# PX4FLOW1_3_1.net
KiCad netlist of a schematic drawn in EAGLE
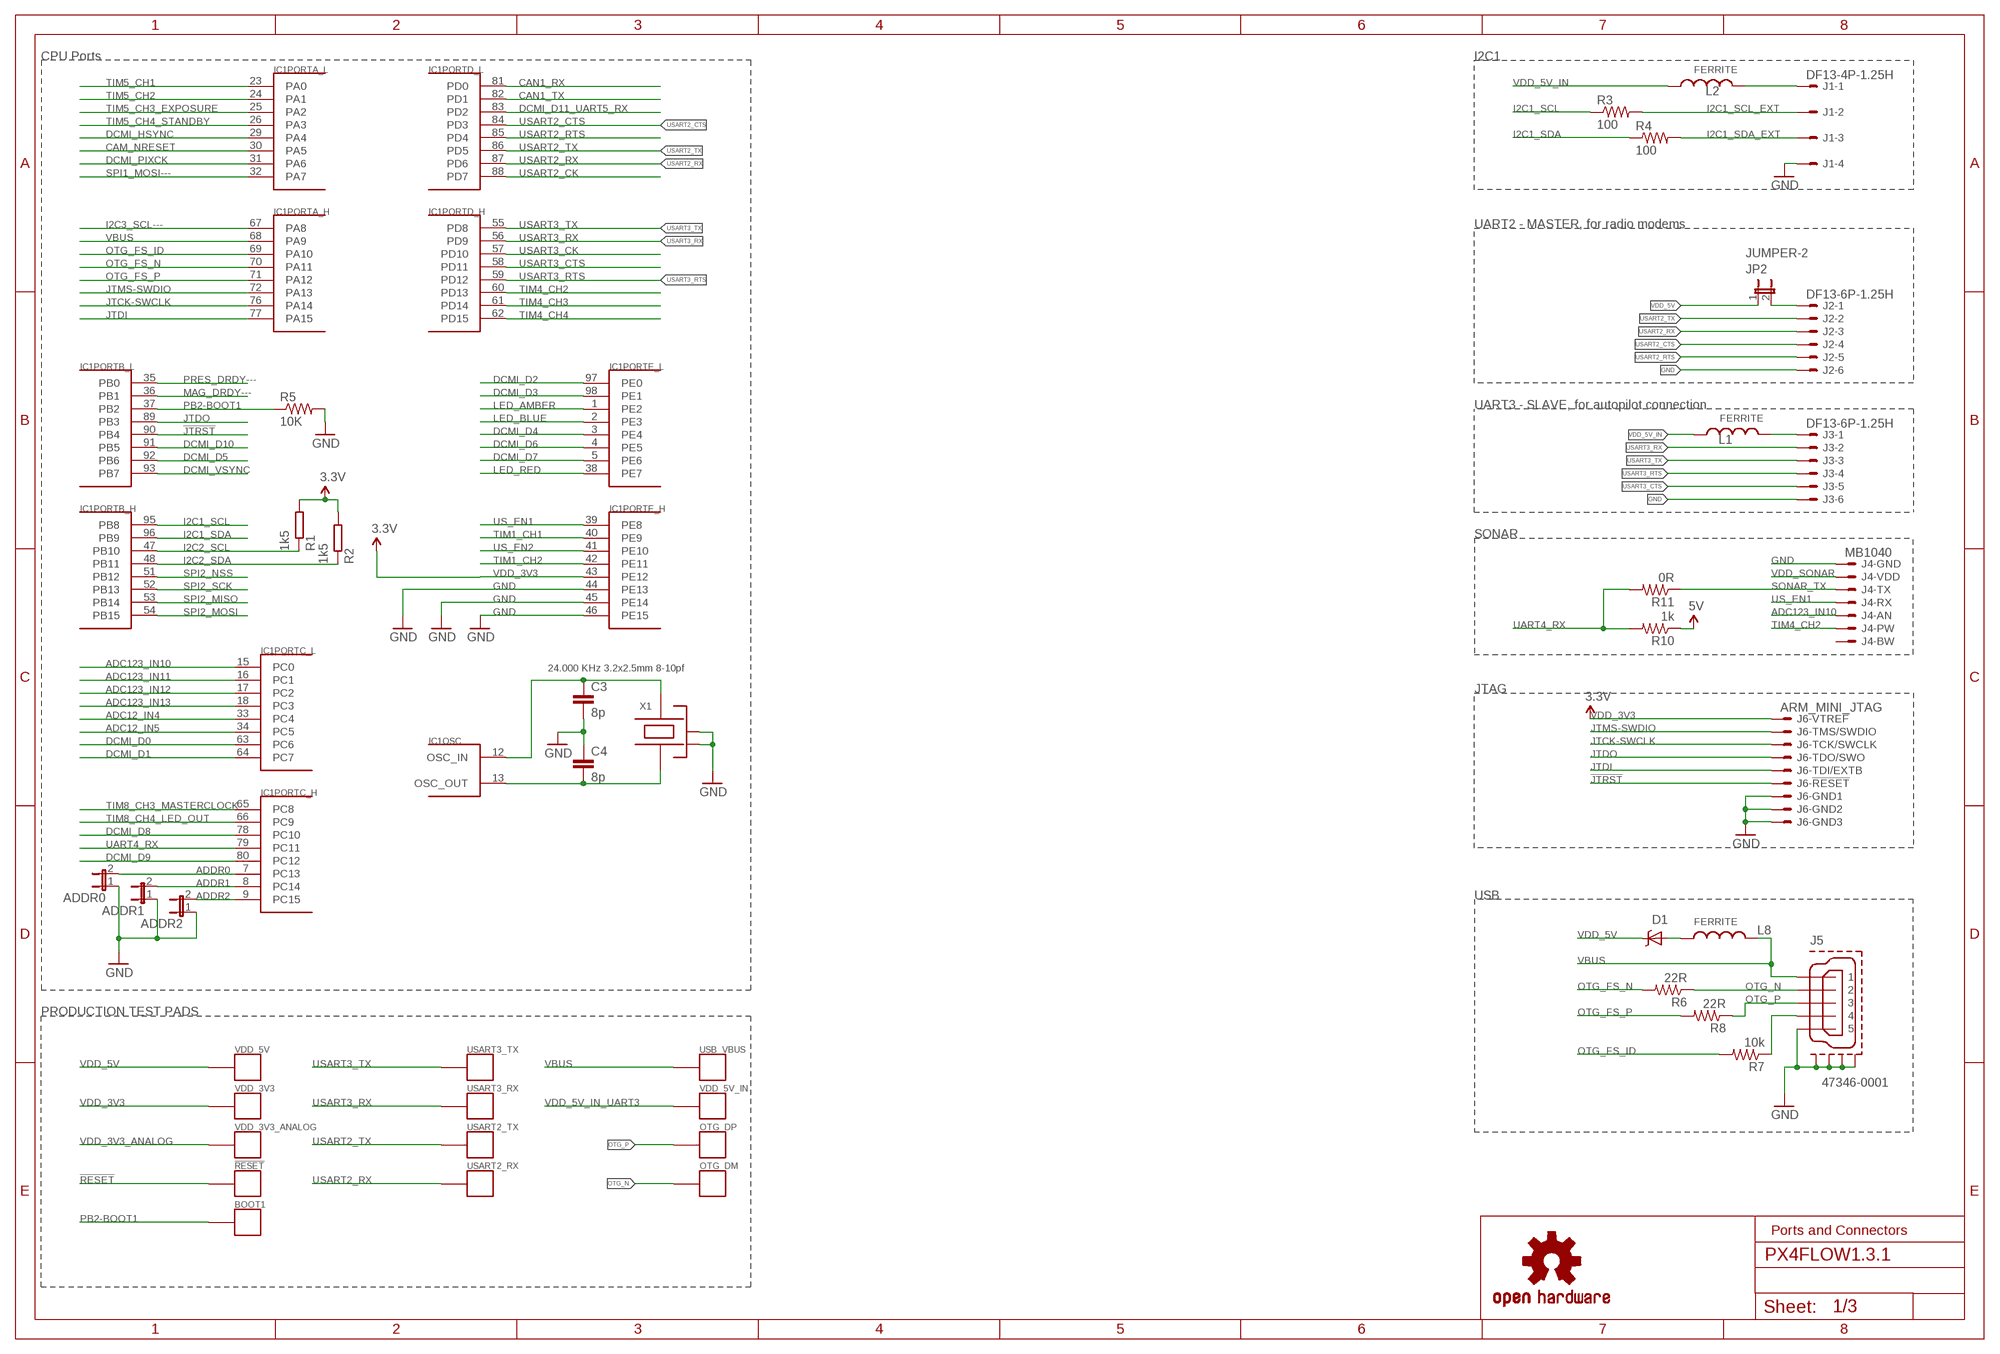
[diagram p0: schematic, sheet 1]
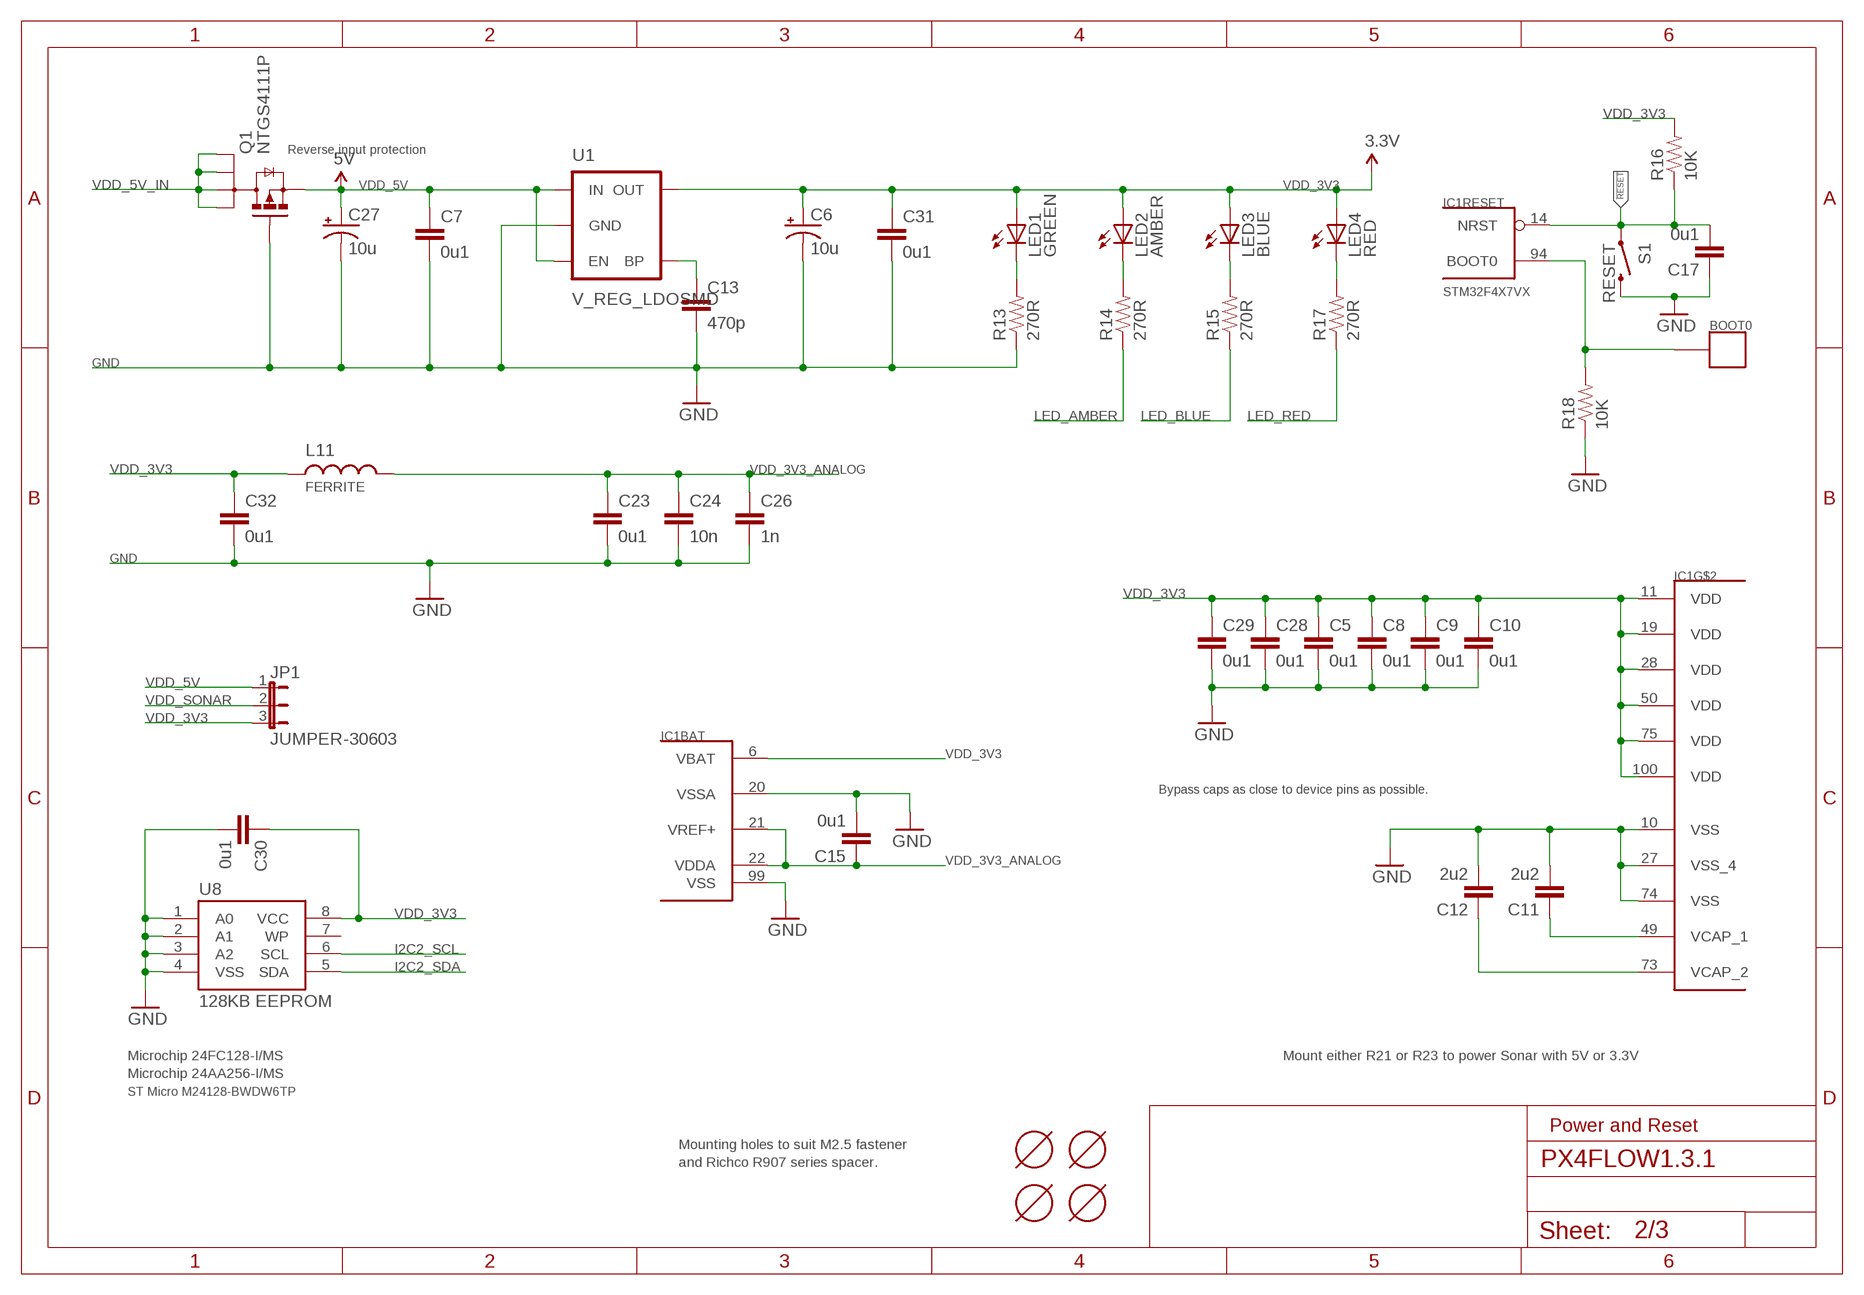
[diagram p1: schematic, sheet 2]
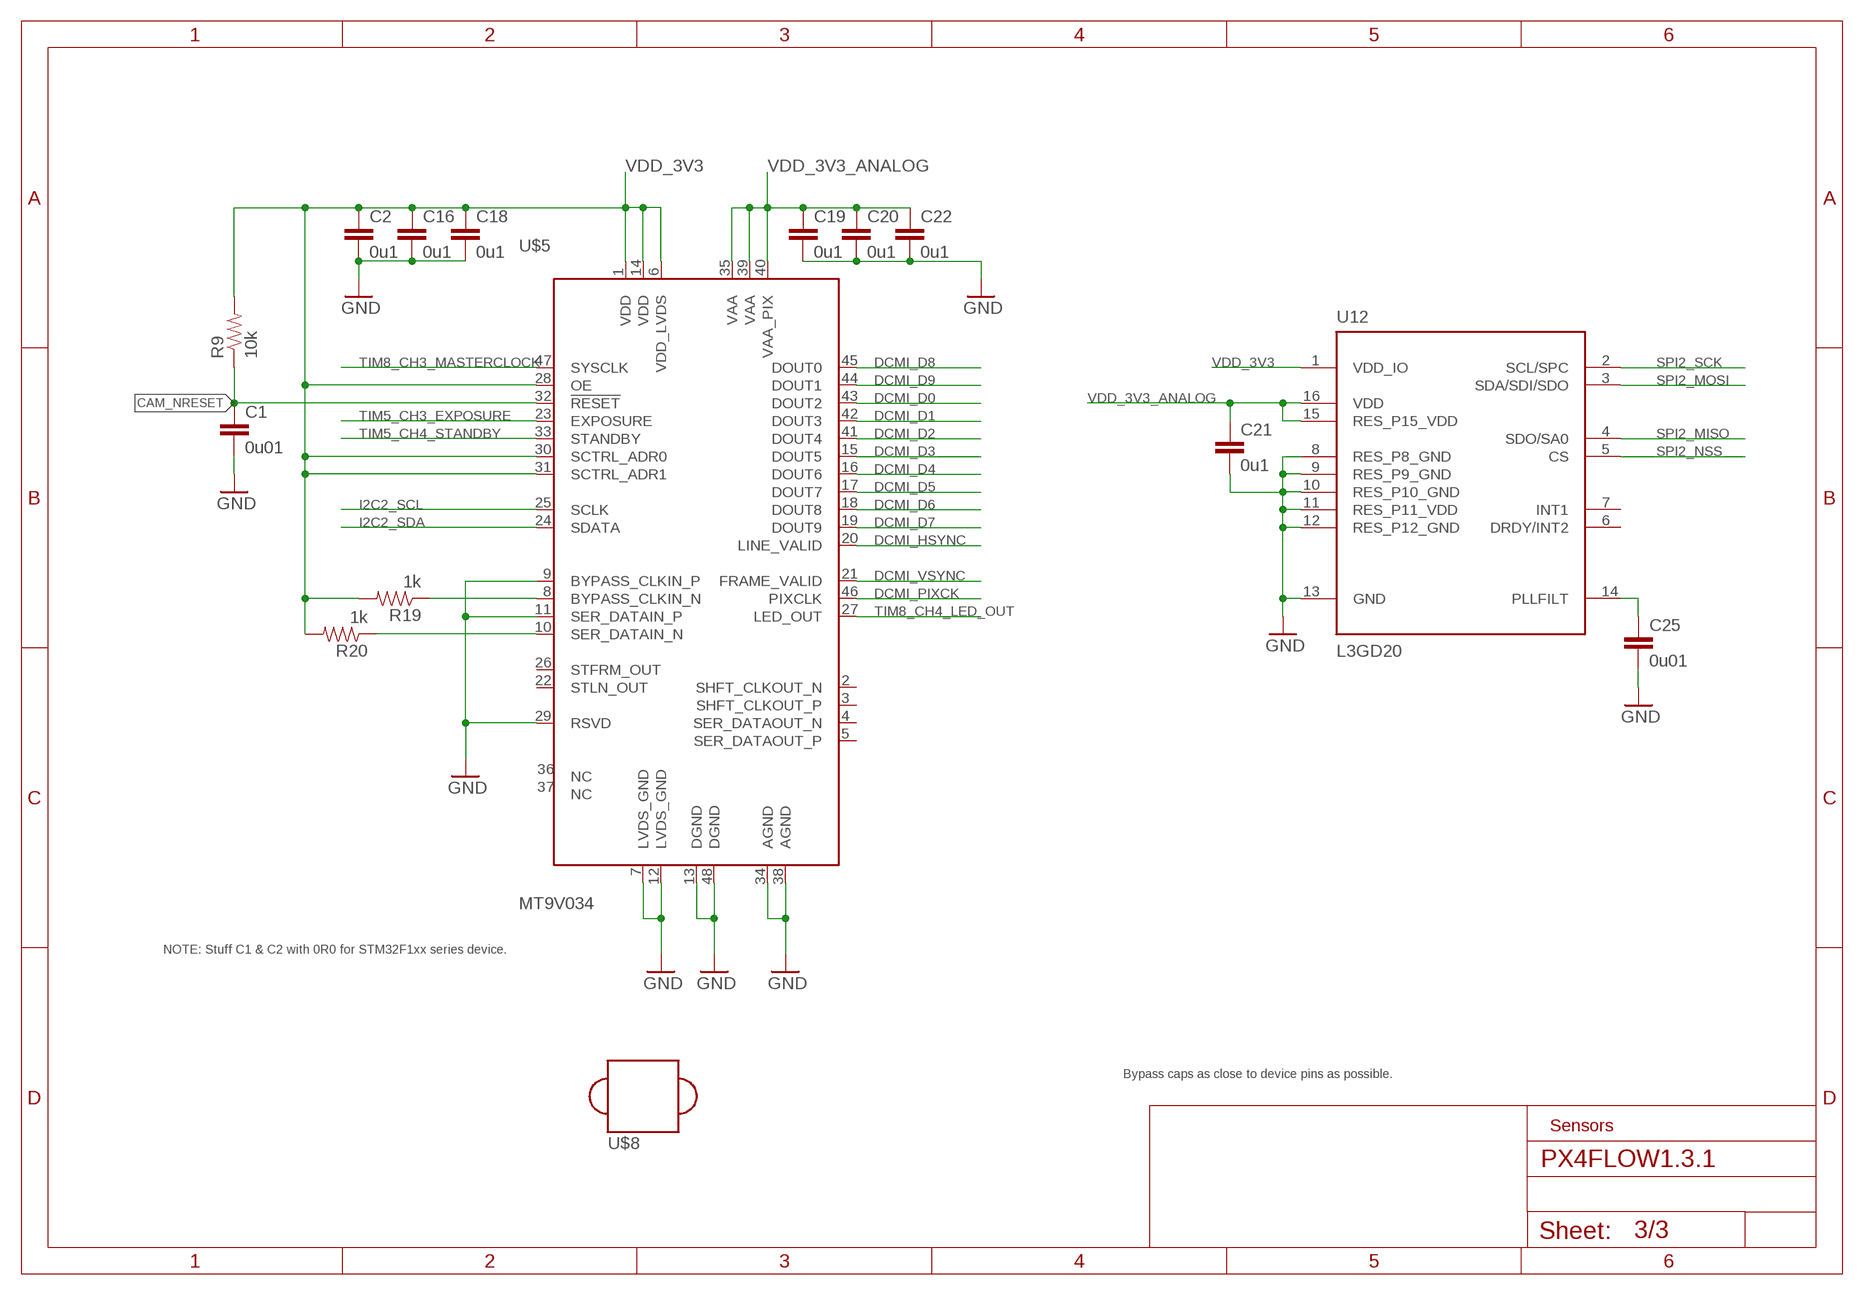
[diagram p2: schematic, sheet 3]

(export (version "E")
  (design (tool "Eeschema 10.0.6"))
  (components
    (comp (ref "BOOT0")
      (value "PAD.05")
      (footprint "eagle-import:PAD.05X.05")
      (libsource (lib "eagle-import") (part "PAD.05"))
    )
    (comp (ref "C5")
      (value "0u1")
      (footprint "eagle-import:0402-CAP")
      (fields (field (name "PARTNO") "CC0402ZRY5V7BB104"))
      (libsource (lib "eagle-import") (part "CAP0402-CAP"))
    )
    (comp (ref "C6")
      (value "10u")
      (footprint "eagle-import:EIA3216")
      (fields (field (name "PARTNO") "F931A106MAA"))
      (libsource (lib "eagle-import") (part "CAP_POL1206"))
    )
    (comp (ref "C7")
      (value "0u1")
      (footprint "eagle-import:0402-CAP")
      (fields (field (name "PARTNO") "CC0402ZRY5V7BB104"))
      (libsource (lib "eagle-import") (part "CAP0402-CAP"))
    )
    (comp (ref "C8")
      (value "0u1")
      (footprint "eagle-import:0402-CAP")
      (fields (field (name "PARTNO") "CC0402ZRY5V7BB104"))
      (libsource (lib "eagle-import") (part "CAP0402-CAP"))
    )
    (comp (ref "C9")
      (value "0u1")
      (footprint "eagle-import:0402-CAP")
      (fields (field (name "PARTNO") "CC0402ZRY5V7BB104"))
      (libsource (lib "eagle-import") (part "CAP0402-CAP"))
    )
    (comp (ref "C10")
      (value "0u1")
      (footprint "eagle-import:0402-CAP")
      (fields (field (name "PARTNO") "CC0402ZRY5V7BB104"))
      (libsource (lib "eagle-import") (part "CAP0402-CAP"))
    )
    (comp (ref "C11")
      (value "2u2")
      (footprint "eagle-import:0402-CAP")
      (fields (field (name "PARTNO") "C1608Y5V1C225Z"))
      (libsource (lib "eagle-import") (part "CAP0402-CAP"))
    )
    (comp (ref "C12")
      (value "2u2")
      (footprint "eagle-import:0402-CAP")
      (fields (field (name "PARTNO") "C1608Y5V1C225Z"))
      (libsource (lib "eagle-import") (part "CAP0402-CAP"))
    )
    (comp (ref "C13")
      (value "470p")
      (footprint "eagle-import:0402-CAP")
      (fields (field (name "PARTNO") "CC0402KRX7R9BB471"))
      (libsource (lib "eagle-import") (part "CAP0402-CAP"))
    )
    (comp (ref "C15")
      (value "0u1")
      (footprint "eagle-import:0402-CAP")
      (fields (field (name "PARTNO") "CC0402ZRY5V7BB104"))
      (libsource (lib "eagle-import") (part "CAP0402-CAP"))
    )
    (comp (ref "C17")
      (value "0u1")
      (footprint "eagle-import:0402-CAP")
      (fields (field (name "PARTNO") "CC0402ZRY5V7BB104"))
      (libsource (lib "eagle-import") (part "CAP0402-CAP"))
    )
    (comp (ref "C23")
      (value "0u1")
      (footprint "eagle-import:0402-CAP")
      (fields (field (name "PARTNO") "CC0402ZRY5V7BB104"))
      (libsource (lib "eagle-import") (part "CAP0402-CAP"))
    )
    (comp (ref "C24")
      (value "10n")
      (footprint "eagle-import:0402-CAP")
      (fields (field (name "PARTNO") "CC0402ZRY5V7BB104"))
      (libsource (lib "eagle-import") (part "CAP0402-CAP"))
    )
    (comp (ref "C26")
      (value "1n")
      (footprint "eagle-import:0402-CAP")
      (fields (field (name "PARTNO") "CC0402ZRY5V7BB104"))
      (libsource (lib "eagle-import") (part "CAP0402-CAP"))
    )
    (comp (ref "C27")
      (value "10u")
      (footprint "eagle-import:EIA3216")
      (fields (field (name "PARTNO") "F931A106MAA"))
      (libsource (lib "eagle-import") (part "CAP_POL1206"))
    )
    (comp (ref "C28")
      (value "0u1")
      (footprint "eagle-import:0402-CAP")
      (fields (field (name "PARTNO") "CC0402ZRY5V7BB104"))
      (libsource (lib "eagle-import") (part "CAP0402-CAP"))
    )
    (comp (ref "C29")
      (value "0u1")
      (footprint "eagle-import:0402-CAP")
      (fields (field (name "PARTNO") "CC0402ZRY5V7BB104"))
      (libsource (lib "eagle-import") (part "CAP0402-CAP"))
    )
    (comp (ref "C30")
      (value "0u1")
      (footprint "eagle-import:0402-CAP")
      (fields (field (name "PARTNO") "CC0402ZRY5V7BB104"))
      (libsource (lib "eagle-import") (part "CAP0402-CAP"))
    )
    (comp (ref "C31")
      (value "0u1")
      (footprint "eagle-import:0402-CAP")
      (fields (field (name "PARTNO") "CC0402ZRY5V7BB104"))
      (libsource (lib "eagle-import") (part "CAP0402-CAP"))
    )
    (comp (ref "C32")
      (value "0u1")
      (footprint "eagle-import:0402-CAP")
      (fields (field (name "PARTNO") "CC0402ZRY5V7BB104"))
      (libsource (lib "eagle-import") (part "CAP0402-CAP"))
    )
    (comp (ref "IC1")
      (value "STM32F4X7VX")
      (footprint "eagle-import:TQFP100")
      (fields (field (name "PARTNO") "STM32F407VGT6"))
      (libsource (lib "eagle-import") (part "STM32F4X7VX"))
    )
    (comp (ref "JP1")
      (value "JUMPER-30603")
      (footprint "eagle-import:SJ_3_0603_PASTE1&2")
      (fields (field (name "PARTNO") "RMCF0402ZT0R00"))
      (libsource (lib "eagle-import") (part "JUMPER-30603"))
    )
    (comp (ref "L11")
      (value "FERRITE")
      (footprint "eagle-import:0402-IND")
      (fields (field (name "PARTNO") "BKP1005HS121-T"))
      (libsource (lib "eagle-import") (part "INDUCTOR0402"))
    )
    (comp (ref "LED1")
      (value "GREEN")
      (footprint "eagle-import:LED-0603")
      (fields (field (name "PARTNO") "LNJ337W83RA"))
      (libsource (lib "eagle-import") (part "LED0603"))
    )
    (comp (ref "LED2")
      (value "AMBER")
      (footprint "eagle-import:LED-0603")
      (fields (field (name "PARTNO") "LNJ437W84RA"))
      (libsource (lib "eagle-import") (part "LED0603"))
    )
    (comp (ref "LED3")
      (value "BLUE")
      (footprint "eagle-import:LED-0603")
      (fields (field (name "PARTNO") "LNJ937W8CRA"))
      (libsource (lib "eagle-import") (part "LED0603"))
    )
    (comp (ref "LED4")
      (value "RED")
      (footprint "eagle-import:LED-0603")
      (fields (field (name "PARTNO") "LNJ237W82RA"))
      (libsource (lib "eagle-import") (part "LED0603"))
    )
    (comp (ref "Q1")
      (value "NTGS4111P")
      (footprint "eagle-import:TSOP-6")
      (libsource (lib "eagle-import") (part "NTGS4111P"))
    )
    (comp (ref "R13")
      (value "270R")
      (footprint "eagle-import:0402-RES")
      (fields (field (name "PARTNO") "MCR01MZPJ271"))
      (libsource (lib "eagle-import") (part "RESISTOR0402-RES"))
    )
    (comp (ref "R14")
      (value "270R")
      (footprint "eagle-import:0402-RES")
      (fields (field (name "PARTNO") "MCR01MZPJ271"))
      (libsource (lib "eagle-import") (part "RESISTOR0402-RES"))
    )
    (comp (ref "R15")
      (value "270R")
      (footprint "eagle-import:0402-RES")
      (fields (field (name "PARTNO") "MCR01MZPJ820"))
      (libsource (lib "eagle-import") (part "RESISTOR0402-RES"))
    )
    (comp (ref "R16")
      (value "10K")
      (footprint "eagle-import:0402-RES")
      (fields (field (name "PARTNO") "RMCF0402FT10K0"))
      (libsource (lib "eagle-import") (part "RESISTOR0402-RES"))
    )
    (comp (ref "R17")
      (value "270R")
      (footprint "eagle-import:0402-RES")
      (fields (field (name "PARTNO") "MCR01MZPJ820"))
      (libsource (lib "eagle-import") (part "RESISTOR0402-RES"))
    )
    (comp (ref "R18")
      (value "10K")
      (footprint "eagle-import:0402-RES")
      (fields (field (name "PARTNO") "RMCF0402FT10K0"))
      (libsource (lib "eagle-import") (part "RESISTOR0402-RES"))
    )
    (comp (ref "S1")
      (value "RESET")
      (footprint "eagle-import:EVQP7J01K")
      (fields (field (name "PARTNO") "EVQP7J01K"))
      (libsource (lib "eagle-import") (part "SWITCH-MOMENTARY-2"))
    )
    (comp (ref "U$1")
      (value "MOUNT-HOLE3.1MM")
      (footprint "eagle-import:MOUNT-HOLE3.1")
      (libsource (lib "eagle-import") (part "MOUNT-HOLE3.1MM"))
    )
    (comp (ref "U$2")
      (value "MOUNT-HOLE3.1MM")
      (footprint "eagle-import:MOUNT-HOLE3.1")
      (libsource (lib "eagle-import") (part "MOUNT-HOLE3.1MM"))
    )
    (comp (ref "U$3")
      (value "MOUNT-HOLE3.1MM")
      (footprint "eagle-import:MOUNT-HOLE3.1")
      (libsource (lib "eagle-import") (part "MOUNT-HOLE3.1MM"))
    )
    (comp (ref "U$4")
      (value "MOUNT-HOLE3.1MM")
      (footprint "eagle-import:MOUNT-HOLE3.1")
      (libsource (lib "eagle-import") (part "MOUNT-HOLE3.1MM"))
    )
    (comp (ref "U1")
      (value "V_REG_LDOSMD")
      (footprint "eagle-import:SOT23-5")
      (fields (field (name "PARTNO") "MIC5207-3.3YM5"))
      (libsource (lib "eagle-import") (part "V_REG_LDOSMD"))
    )
    (comp (ref "U8")
      (value "128KB EEPROM")
      (footprint "eagle-import:MSOP-8")
      (fields (field (name "PARTNO") "24FC128-I/MS"))
      (libsource (lib "eagle-import") (part "EEPROM-I2CMSOP"))
    )
    (comp (ref "C1")
      (value "0u01")
      (footprint "eagle-import:0402-CAP")
      (fields (field (name "PARTNO") "CC0402KRX7R7BB103"))
      (libsource (lib "eagle-import") (part "CAP0402-CAP"))
    )
    (comp (ref "C2")
      (value "0u1")
      (footprint "eagle-import:0402-CAP")
      (fields (field (name "PARTNO") "CC0402ZRY5V7BB104"))
      (libsource (lib "eagle-import") (part "CAP0402-CAP"))
    )
    (comp (ref "C16")
      (value "0u1")
      (footprint "eagle-import:0402-CAP")
      (fields (field (name "PARTNO") "CC0402ZRY5V7BB104"))
      (libsource (lib "eagle-import") (part "CAP0402-CAP"))
    )
    (comp (ref "C18")
      (value "0u1")
      (footprint "eagle-import:0402-CAP")
      (fields (field (name "PARTNO") "CC0402ZRY5V7BB104"))
      (libsource (lib "eagle-import") (part "CAP0402-CAP"))
    )
    (comp (ref "C19")
      (value "0u1")
      (footprint "eagle-import:0402-CAP")
      (fields (field (name "PARTNO") "CC0402ZRY5V7BB104"))
      (libsource (lib "eagle-import") (part "CAP0402-CAP"))
    )
    (comp (ref "C20")
      (value "0u1")
      (footprint "eagle-import:0402-CAP")
      (fields (field (name "PARTNO") "CC0402ZRY5V7BB104"))
      (libsource (lib "eagle-import") (part "CAP0402-CAP"))
    )
    (comp (ref "C21")
      (value "0u1")
      (footprint "eagle-import:0402-CAP")
      (fields (field (name "PARTNO") "CC0402ZRY5V7BB104"))
      (libsource (lib "eagle-import") (part "CAP0402-CAP"))
    )
    (comp (ref "C22")
      (value "0u1")
      (footprint "eagle-import:0402-CAP")
      (fields (field (name "PARTNO") "CC0402ZRY5V7BB104"))
      (libsource (lib "eagle-import") (part "CAP0402-CAP"))
    )
    (comp (ref "C25")
      (value "0u01")
      (footprint "eagle-import:0402-CAP")
      (fields (field (name "PARTNO") "CC0402KRX7R7BB103"))
      (libsource (lib "eagle-import") (part "CAP0402-CAP"))
    )
    (comp (ref "R9")
      (value "10k")
      (footprint "eagle-import:0402-RES")
      (fields (field (name "PARTNO") "MCR01MZPJ271"))
      (libsource (lib "eagle-import") (part "RESISTOR0402-RES"))
    )
    (comp (ref "R19")
      (value "1k")
      (footprint "eagle-import:0402-RES")
      (fields (field (name "PARTNO") "RMCF0402JT1K00"))
      (libsource (lib "eagle-import") (part "RESISTOR0402-RES"))
    )
    (comp (ref "R20")
      (value "1k")
      (footprint "eagle-import:0402-RES")
      (fields (field (name "PARTNO") "RMCF0402JT1K00"))
      (libsource (lib "eagle-import") (part "RESISTOR0402-RES"))
    )
    (comp (ref "U$5")
      (value "MT9V034")
      (footprint "eagle-import:CLCC-48")
      (fields (field (name "PARTNO") "MT9V034C12STM"))
      (libsource (lib "eagle-import") (part "MT9V034"))
    )
    (comp (ref "U$8")
      (value "LENSMOUNT_M12")
      (footprint "eagle-import:LENSMOUNT_LARGE_M12")
      (libsource (lib "eagle-import") (part "LENSMOUNT_M12"))
    )
    (comp (ref "U12")
      (value "L3GD20")
      (footprint "eagle-import:L3G4200DH-MAN")
      (libsource (lib "eagle-import") (part "L3G4200DH-LL"))
    )
    (comp (ref "!RESET")
      (value "PAD.04")
      (footprint "eagle-import:PAD.04X.04")
      (libsource (lib "eagle-import") (part "PAD.04"))
    )
    (comp (ref "ADDR0")
      (value "JUMPER-2")
      (footprint "eagle-import:SJ_2")
      (libsource (lib "eagle-import") (part "JUMPER-2"))
    )
    (comp (ref "ADDR1")
      (value "JUMPER-2")
      (footprint "eagle-import:SJ_2")
      (libsource (lib "eagle-import") (part "JUMPER-2"))
    )
    (comp (ref "ADDR2")
      (value "JUMPER-2")
      (footprint "eagle-import:SJ_2")
      (libsource (lib "eagle-import") (part "JUMPER-2"))
    )
    (comp (ref "BOOT1")
      (value "PAD.04")
      (footprint "eagle-import:PAD.04X.04")
      (libsource (lib "eagle-import") (part "PAD.04"))
    )
    (comp (ref "C3")
      (value "8p")
      (footprint "eagle-import:0402-CAP")
      (libsource (lib "eagle-import") (part "CAPACITOR-0402"))
    )
    (comp (ref "C4")
      (value "8p")
      (footprint "eagle-import:0402-CAP")
      (libsource (lib "eagle-import") (part "CAPACITOR-0402"))
    )
    (comp (ref "D1")
      (value "MSS1P4-M3")
      (footprint "eagle-import:MICROSMP")
      (fields (field (name "PARTNO") "MSS1P4-M3/89A"))
      (libsource (lib "eagle-import") (part "DIODE-SCHOTTKY_MSMP"))
    )
    (comp (ref "J1")
      (value "DF13-4P-1.25H")
      (footprint "eagle-import:DF13A-4P-1.25H")
      (fields (field (name "PARTNO") "DF13A-4P-1.25H(20)"))
      (libsource (lib "eagle-import") (part "DF13-4P-1.25?H"))
    )
    (comp (ref "J2")
      (value "DF13-6P-1.25H")
      (footprint "eagle-import:DF13A-6P-1.25H")
      (fields (field (name "PARTNO") "DF13A-6P-1.25H(20)"))
      (libsource (lib "eagle-import") (part "DF13-6P-1.25?H"))
    )
    (comp (ref "J3")
      (value "DF13-6P-1.25H")
      (footprint "eagle-import:DF13A-6P-1.25H")
      (fields (field (name "PARTNO") "DF13A-6P-1.25H(20)"))
      (libsource (lib "eagle-import") (part "DF13-6P-1.25?H"))
    )
    (comp (ref "J4")
      (value "MB1040")
      (footprint "eagle-import:MAXSONAR")
      (fields (field (name "BOM") "EXCLUDE") (field (name "PARTNO") "*"))
      (libsource (lib "eagle-import") (part "MAXSONAR"))
    )
    (comp (ref "J5")
      (value "47346-0001")
      (footprint "eagle-import:MOLEX-47346-0001")
      (libsource (lib "eagle-import") (part "MOLEX-47346-0001"))
    )
    (comp (ref "J6")
      (value "ARM_MINI_JTAG")
      (footprint "eagle-import:FTSH-105-01-XXX-DV-K")
      (fields (field (name "PARTNO") "M50-3900542"))
      (libsource (lib "eagle-import") (part "ARM_MINI_JTAG-SMT"))
    )
    (comp (ref "JP2")
      (value "JUMPER-2")
      (footprint "eagle-import:SJ_2")
      (libsource (lib "eagle-import") (part "JUMPER-2"))
    )
    (comp (ref "L1")
      (value "FERRITE")
      (footprint "eagle-import:0402-IND")
      (fields (field (name "PARTNO") "BKP1005HS121-T"))
      (libsource (lib "eagle-import") (part "INDUCTOR0402"))
    )
    (comp (ref "L2")
      (value "FERRITE")
      (footprint "eagle-import:0402-IND")
      (fields (field (name "PARTNO") "BKP1005HS121-T"))
      (libsource (lib "eagle-import") (part "INDUCTOR0402"))
    )
    (comp (ref "L8")
      (value "FERRITE")
      (footprint "eagle-import:0402-IND")
      (fields (field (name "PARTNO") "BKP1005HS121-T"))
      (libsource (lib "eagle-import") (part "INDUCTOR0402"))
    )
    (comp (ref "OTG_DM")
      (value "PAD.04")
      (footprint "eagle-import:PAD.04X.04")
      (libsource (lib "eagle-import") (part "PAD.04"))
    )
    (comp (ref "OTG_DP")
      (value "PAD.04")
      (footprint "eagle-import:PAD.04X.04")
      (libsource (lib "eagle-import") (part "PAD.04"))
    )
    (comp (ref "R1")
      (value "1k5")
      (footprint "eagle-import:0402-RES")
      (libsource (lib "eagle-import") (part "RESISTOR-0402"))
    )
    (comp (ref "R2")
      (value "1k5")
      (footprint "eagle-import:0402-RES")
      (libsource (lib "eagle-import") (part "RESISTOR-0402"))
    )
    (comp (ref "R3")
      (value "100")
      (footprint "eagle-import:0402-RES")
      (fields (field (name "PARTNO") "RMCF0402JT100R"))
      (libsource (lib "eagle-import") (part "RESISTOR0402-RES"))
    )
    (comp (ref "R4")
      (value "100")
      (footprint "eagle-import:0402-RES")
      (fields (field (name "PARTNO") "RMCF0402JT100R"))
      (libsource (lib "eagle-import") (part "RESISTOR0402-RES"))
    )
    (comp (ref "R5")
      (value "10K")
      (footprint "eagle-import:0402-RES")
      (fields (field (name "PARTNO") "RMCF0402FT10K0"))
      (libsource (lib "eagle-import") (part "RESISTOR0402-RES"))
    )
    (comp (ref "R6")
      (value "22R")
      (footprint "eagle-import:0402-RES")
      (fields (field (name "PARTNO") "RMCF0402JT22R0"))
      (libsource (lib "eagle-import") (part "RESISTOR0402-RES"))
    )
    (comp (ref "R7")
      (value "10k")
      (footprint "eagle-import:0402-RES")
      (fields (field (name "PARTNO") "MFR-25FBF-10K0"))
      (libsource (lib "eagle-import") (part "RESISTOR0402-RES"))
    )
    (comp (ref "R8")
      (value "22R")
      (footprint "eagle-import:0402-RES")
      (fields (field (name "PARTNO") "RMCF0402JT22R0"))
      (libsource (lib "eagle-import") (part "RESISTOR0402-RES"))
    )
    (comp (ref "R10")
      (value "1k")
      (footprint "eagle-import:0402-RES")
      (fields (field (name "PARTNO") "RMCF0402JT1K00"))
      (libsource (lib "eagle-import") (part "RESISTOR0402-RES"))
    )
    (comp (ref "R11")
      (value "0R")
      (footprint "eagle-import:0402-RES")
      (fields (field (name "PARTNO") "RMCF0402JT1K00"))
      (libsource (lib "eagle-import") (part "RESISTOR0402-RES"))
    )
    (comp (ref "U$10")
      (value "OSHW-LOGOS")
      (footprint "eagle-import:OSHW-LOGO-S")
      (libsource (lib "eagle-import") (part "OSHW-LOGOS"))
    )
    (comp (ref "USART2_RX")
      (value "PAD.04")
      (footprint "eagle-import:PAD.04X.04")
      (libsource (lib "eagle-import") (part "PAD.04"))
    )
    (comp (ref "USART2_TX")
      (value "PAD.04")
      (footprint "eagle-import:PAD.04X.04")
      (libsource (lib "eagle-import") (part "PAD.04"))
    )
    (comp (ref "USART3_RX")
      (value "PAD.04")
      (footprint "eagle-import:PAD.04X.04")
      (libsource (lib "eagle-import") (part "PAD.04"))
    )
    (comp (ref "USART3_TX")
      (value "PAD.04")
      (footprint "eagle-import:PAD.04X.04")
      (libsource (lib "eagle-import") (part "PAD.04"))
    )
    (comp (ref "USB_VBUS")
      (value "PAD.04")
      (footprint "eagle-import:PAD.04X.04")
      (libsource (lib "eagle-import") (part "PAD.04"))
    )
    (comp (ref "VDD_3V3")
      (value "PAD.04")
      (footprint "eagle-import:PAD.04X.04")
      (libsource (lib "eagle-import") (part "PAD.04"))
    )
    (comp (ref "VDD_3V3_ANALOG")
      (value "PAD.04")
      (footprint "eagle-import:PAD.04X.04")
      (libsource (lib "eagle-import") (part "PAD.04"))
    )
    (comp (ref "VDD_5V")
      (value "PAD.04")
      (footprint "eagle-import:PAD.04X.04")
      (libsource (lib "eagle-import") (part "PAD.04"))
    )
    (comp (ref "VDD_5V_IN")
      (value "PAD.04")
      (footprint "eagle-import:PAD.04X.04")
      (libsource (lib "eagle-import") (part "PAD.04"))
    )
    (comp (ref "X1")
      (value "24.000 KHz 3.2x2.5mm 8-10pf")
      (footprint "eagle-import:OSCILLATOR-3.2X2.5")
      (fields (field (name "PARTNO") "NX3225SA-24.000000MHZ"))
      (libsource (lib "eagle-import") (part "OSCILLATOR-3.2X2.5"))
    )
  )
  (nets
    (net (code "1") (name "ADC12_IN4") (class "Default")
      (node (ref "IC1") (pin "33") (pinfunction "PC4_33") (pintype "bidirectional"))
    )
    (net (code "2") (name "ADC12_IN5") (class "Default")
      (node (ref "IC1") (pin "34") (pinfunction "PC5_34") (pintype "bidirectional"))
    )
    (net (code "3") (name "ADC123_IN10") (class "Default")
      (node (ref "IC1") (pin "15") (pinfunction "PC0_15") (pintype "bidirectional"))
      (node (ref "J4") (pin "AN") (pinfunction "S_AN") (pintype "passive"))
    )
    (net (code "4") (name "ADC123_IN11") (class "Default")
      (node (ref "IC1") (pin "16") (pinfunction "PC1_16") (pintype "bidirectional"))
    )
    (net (code "5") (name "ADC123_IN12") (class "Default")
      (node (ref "IC1") (pin "17") (pinfunction "PC2_17") (pintype "bidirectional"))
    )
    (net (code "6") (name "ADC123_IN13") (class "Default")
      (node (ref "IC1") (pin "18") (pinfunction "PC3_18") (pintype "bidirectional"))
    )
    (net (code "7") (name "ADDR0") (class "Default")
      (node (ref "ADDR0") (pin "2") (pinfunction "2_2") (pintype "passive"))
      (node (ref "IC1") (pin "7") (pinfunction "PC13_7") (pintype "bidirectional"))
    )
    (net (code "8") (name "ADDR1") (class "Default")
      (node (ref "ADDR1") (pin "2") (pinfunction "2_2") (pintype "passive"))
      (node (ref "IC1") (pin "8") (pinfunction "PC14_8") (pintype "bidirectional"))
    )
    (net (code "9") (name "ADDR2") (class "Default")
      (node (ref "ADDR2") (pin "2") (pinfunction "2_2") (pintype "passive"))
      (node (ref "IC1") (pin "9") (pinfunction "PC15_9") (pintype "bidirectional"))
    )
    (net (code "10") (name "CAM_NRESET") (class "Default")
      (node (ref "C1") (pin "1") (pinfunction "1_1") (pintype "passive"))
      (node (ref "IC1") (pin "30") (pinfunction "PA5_30") (pintype "bidirectional"))
      (node (ref "R9") (pin "1") (pinfunction "1_1") (pintype "passive"))
      (node (ref "U$5") (pin "32") (pinfunction "~{RESET}_32") (pintype "input"))
    )
    (net (code "11") (name "CAN1_RX") (class "Default")
      (node (ref "IC1") (pin "81") (pinfunction "PD0_81") (pintype "bidirectional"))
    )
    (net (code "12") (name "CAN1_TX") (class "Default")
      (node (ref "IC1") (pin "82") (pinfunction "PD1_82") (pintype "bidirectional"))
    )
    (net (code "13") (name "DCMI_D0") (class "Default")
      (node (ref "IC1") (pin "63") (pinfunction "PC6_63") (pintype "bidirectional"))
      (node (ref "U$5") (pin "43") (pinfunction "DOUT2_43") (pintype "output"))
    )
    (net (code "14") (name "DCMI_D1") (class "Default")
      (node (ref "IC1") (pin "64") (pinfunction "PC7_64") (pintype "bidirectional"))
      (node (ref "U$5") (pin "42") (pinfunction "DOUT3_42") (pintype "output"))
    )
    (net (code "15") (name "DCMI_D2") (class "Default")
      (node (ref "IC1") (pin "97") (pinfunction "PE0_97") (pintype "bidirectional"))
      (node (ref "U$5") (pin "41") (pinfunction "DOUT4_41") (pintype "output"))
    )
    (net (code "16") (name "DCMI_D3") (class "Default")
      (node (ref "IC1") (pin "98") (pinfunction "PE1_98") (pintype "bidirectional"))
      (node (ref "U$5") (pin "15") (pinfunction "DOUT5_15") (pintype "output"))
    )
    (net (code "17") (name "DCMI_D4") (class "Default")
      (node (ref "IC1") (pin "3") (pinfunction "PE4_3") (pintype "bidirectional"))
      (node (ref "U$5") (pin "16") (pinfunction "DOUT6_16") (pintype "output"))
    )
    (net (code "18") (name "DCMI_D5") (class "Default")
      (node (ref "IC1") (pin "92") (pinfunction "PB6_92") (pintype "bidirectional"))
      (node (ref "U$5") (pin "17") (pinfunction "DOUT7_17") (pintype "output"))
    )
    (net (code "19") (name "DCMI_D6") (class "Default")
      (node (ref "IC1") (pin "4") (pinfunction "PE5_4") (pintype "bidirectional"))
      (node (ref "U$5") (pin "18") (pinfunction "DOUT8_18") (pintype "output"))
    )
    (net (code "20") (name "DCMI_D7") (class "Default")
      (node (ref "IC1") (pin "5") (pinfunction "PE6_5") (pintype "bidirectional"))
      (node (ref "U$5") (pin "19") (pinfunction "DOUT9_19") (pintype "output"))
    )
    (net (code "21") (name "DCMI_D8") (class "Default")
      (node (ref "IC1") (pin "78") (pinfunction "PC10_78") (pintype "bidirectional"))
      (node (ref "U$5") (pin "45") (pinfunction "DOUT0_45") (pintype "output"))
    )
    (net (code "22") (name "DCMI_D9") (class "Default")
      (node (ref "IC1") (pin "80") (pinfunction "PC12_80") (pintype "bidirectional"))
      (node (ref "U$5") (pin "44") (pinfunction "DOUT1_44") (pintype "output"))
    )
    (net (code "23") (name "DCMI_D10") (class "Default")
      (node (ref "IC1") (pin "91") (pinfunction "PB5_91") (pintype "bidirectional"))
    )
    (net (code "24") (name "DCMI_D11_UART5_RX") (class "Default")
      (node (ref "IC1") (pin "83") (pinfunction "PD2_83") (pintype "bidirectional"))
    )
    (net (code "25") (name "DCMI_HSYNC") (class "Default")
      (node (ref "IC1") (pin "29") (pinfunction "PA4_29") (pintype "bidirectional"))
      (node (ref "U$5") (pin "20") (pinfunction "LINE_VALID_20") (pintype "output"))
    )
    (net (code "26") (name "DCMI_PIXCK") (class "Default")
      (node (ref "IC1") (pin "31") (pinfunction "PA6_31") (pintype "bidirectional"))
      (node (ref "U$5") (pin "46") (pinfunction "PIXCLK_46") (pintype "output"))
    )
    (net (code "27") (name "DCMI_VSYNC") (class "Default")
      (node (ref "IC1") (pin "93") (pinfunction "PB7_93") (pintype "bidirectional"))
      (node (ref "U$5") (pin "21") (pinfunction "FRAME_VALID_21") (pintype "output"))
    )
    (net (code "28") (name "GND") (class "Default")
      (node (ref "ADDR0") (pin "1") (pinfunction "1_1") (pintype "passive"))
      (node (ref "ADDR1") (pin "1") (pinfunction "1_1") (pintype "passive"))
      (node (ref "ADDR2") (pin "1") (pinfunction "1_1") (pintype "passive"))
      (node (ref "C1") (pin "2") (pinfunction "2_2") (pintype "passive"))
      (node (ref "C10") (pin "2") (pinfunction "2_2") (pintype "passive"))
      (node (ref "C11") (pin "2") (pinfunction "2_2") (pintype "passive"))
      (node (ref "C12") (pin "2") (pinfunction "2_2") (pintype "passive"))
      (node (ref "C13") (pin "2") (pinfunction "2_2") (pintype "passive"))
      (node (ref "C15") (pin "2") (pinfunction "2_2") (pintype "passive"))
      (node (ref "C16") (pin "2") (pinfunction "2_2") (pintype "passive"))
      (node (ref "C17") (pin "1") (pinfunction "1_1") (pintype "passive"))
      (node (ref "C18") (pin "2") (pinfunction "2_2") (pintype "passive"))
      (node (ref "C19") (pin "2") (pinfunction "2_2") (pintype "passive"))
      (node (ref "C2") (pin "2") (pinfunction "2_2") (pintype "passive"))
      (node (ref "C20") (pin "2") (pinfunction "2_2") (pintype "passive"))
      (node (ref "C21") (pin "2") (pinfunction "2_2") (pintype "passive"))
      (node (ref "C22") (pin "2") (pinfunction "2_2") (pintype "passive"))
      (node (ref "C23") (pin "2") (pinfunction "2_2") (pintype "passive"))
      (node (ref "C24") (pin "2") (pinfunction "2_2") (pintype "passive"))
      (node (ref "C25") (pin "2") (pinfunction "2_2") (pintype "passive"))
      (node (ref "C26") (pin "2") (pinfunction "2_2") (pintype "passive"))
      (node (ref "C27") (pin "C") (pinfunction "-_C") (pintype "passive"))
      (node (ref "C28") (pin "2") (pinfunction "2_2") (pintype "passive"))
      (node (ref "C29") (pin "2") (pinfunction "2_2") (pintype "passive"))
      (node (ref "C3") (pin "P$2") (pinfunction "2_P$2") (pintype "passive"))
      (node (ref "C30") (pin "2") (pinfunction "2_2") (pintype "passive"))
      (node (ref "C31") (pin "2") (pinfunction "2_2") (pintype "passive"))
      (node (ref "C32") (pin "2") (pinfunction "2_2") (pintype "passive"))
      (node (ref "C4") (pin "P$1") (pinfunction "1_P$1") (pintype "passive"))
      (node (ref "C5") (pin "2") (pinfunction "2_2") (pintype "passive"))
      (node (ref "C6") (pin "C") (pinfunction "-_C") (pintype "passive"))
      (node (ref "C7") (pin "2") (pinfunction "2_2") (pintype "passive"))
      (node (ref "C8") (pin "2") (pinfunction "2_2") (pintype "passive"))
      (node (ref "C9") (pin "2") (pinfunction "2_2") (pintype "passive"))
      (node (ref "IC1") (pin "10") (pinfunction "VSS_10") (pintype "power_in"))
      (node (ref "IC1") (pin "20") (pinfunction "VSSA_20") (pintype "power_in"))
      (node (ref "IC1") (pin "27") (pinfunction "VSS_4_27") (pintype "power_in"))
      (node (ref "IC1") (pin "44") (pinfunction "PE13_44") (pintype "bidirectional"))
      (node (ref "IC1") (pin "45") (pinfunction "PE14_45") (pintype "bidirectional"))
      (node (ref "IC1") (pin "46") (pinfunction "PE15_46") (pintype "bidirectional"))
      (node (ref "IC1") (pin "74") (pinfunction "VSS_74") (pintype "power_in"))
      (node (ref "IC1") (pin "99") (pinfunction "VSS_99") (pintype "power_in"))
      (node (ref "J1") (pin "4") (pinfunction "S_4") (pintype "passive"))
      (node (ref "J2") (pin "6") (pinfunction "S_6") (pintype "passive"))
      (node (ref "J3") (pin "6") (pinfunction "S_6") (pintype "passive"))
      (node (ref "J4") (pin "GND") (pinfunction "S_GND") (pintype "passive"))
      (node (ref "J5") (pin "GND") (pinfunction "5_GND") (pintype "power_in"))
      (node (ref "J5") (pin "GND1") (pinfunction "GND1_GND1") (pintype "bidirectional"))
      (node (ref "J5") (pin "GND2") (pinfunction "GND2_GND2") (pintype "bidirectional"))
      (node (ref "J5") (pin "GND3") (pinfunction "GND3_GND3") (pintype "bidirectional"))
      (node (ref "J5") (pin "GND4") (pinfunction "GND4_GND4") (pintype "bidirectional"))
      (node (ref "J6") (pin "3") (pinfunction "S_3") (pintype "passive"))
      (node (ref "J6") (pin "5") (pinfunction "S_5") (pintype "passive"))
      (node (ref "J6") (pin "9") (pinfunction "S_9") (pintype "passive"))
      (node (ref "Q1") (pin "3") (pinfunction "G_3") (pintype "passive"))
      (node (ref "R13") (pin "1") (pinfunction "1_1") (pintype "passive"))
      (node (ref "R18") (pin "1") (pinfunction "1_1") (pintype "passive"))
      (node (ref "R5") (pin "2") (pinfunction "2_2") (pintype "passive"))
      (node (ref "S1") (pin "B3") (pinfunction "2_B3") (pintype "passive"))
      (node (ref "U$5") (pin "11") (pinfunction "SER_DATAIN_P_11") (pintype "input"))
      (node (ref "U$5") (pin "12") (pinfunction "LVDS_GND_12") (pintype "power_in"))
      (node (ref "U$5") (pin "13") (pinfunction "DGND_13") (pintype "power_in"))
      (node (ref "U$5") (pin "29") (pinfunction "RSVD_29") (pintype "input"))
      (node (ref "U$5") (pin "34") (pinfunction "AGND_34") (pintype "power_in"))
      (node (ref "U$5") (pin "38") (pinfunction "AGND_38") (pintype "power_in"))
      (node (ref "U$5") (pin "48") (pinfunction "DGND_48") (pintype "power_in"))
      (node (ref "U$5") (pin "7") (pinfunction "LVDS_GND_7") (pintype "power_in"))
      (node (ref "U$5") (pin "9") (pinfunction "BYPASS_CLKIN_P_9") (pintype "input"))
      (node (ref "U1") (pin "2") (pinfunction "GND_2") (pintype "input"))
      (node (ref "U12") (pin "10") (pinfunction "RES_P10_GND_10") (pintype "bidirectional"))
      (node (ref "U12") (pin "11") (pinfunction "RES_P11_VDD_11") (pintype "bidirectional"))
      (node (ref "U12") (pin "12") (pinfunction "RES_P12_GND_12") (pintype "bidirectional"))
      (node (ref "U12") (pin "13") (pinfunction "GND_13") (pintype "bidirectional"))
      (node (ref "U12") (pin "8") (pinfunction "RES_P8_GND_8") (pintype "bidirectional"))
      (node (ref "U12") (pin "9") (pinfunction "RES_P9_GND_9") (pintype "bidirectional"))
      (node (ref "U8") (pin "1") (pinfunction "A0_1") (pintype "bidirectional"))
      (node (ref "U8") (pin "2") (pinfunction "A1_2") (pintype "bidirectional"))
      (node (ref "U8") (pin "3") (pinfunction "A2_3") (pintype "bidirectional"))
      (node (ref "U8") (pin "4") (pinfunction "VSS_4") (pintype "power_in"))
      (node (ref "X1") (pin "2") (pinfunction "NC_2_2") (pintype "power_in"))
      (node (ref "X1") (pin "4") (pinfunction "NC_4_4") (pintype "power_in"))
    )
    (net (code "29") (name "I2C1_SCL") (class "Default")
      (node (ref "IC1") (pin "95") (pinfunction "PB8_95") (pintype "bidirectional"))
      (node (ref "R3") (pin "1") (pinfunction "1_1") (pintype "passive"))
    )
    (net (code "30") (name "I2C1_SCL_EXT") (class "Default")
      (node (ref "J1") (pin "2") (pinfunction "S_2") (pintype "passive"))
      (node (ref "R3") (pin "2") (pinfunction "2_2") (pintype "passive"))
    )
    (net (code "31") (name "I2C1_SDA") (class "Default")
      (node (ref "IC1") (pin "96") (pinfunction "PB9_96") (pintype "bidirectional"))
      (node (ref "R4") (pin "1") (pinfunction "1_1") (pintype "passive"))
    )
    (net (code "32") (name "I2C1_SDA_EXT") (class "Default")
      (node (ref "J1") (pin "3") (pinfunction "S_3") (pintype "passive"))
      (node (ref "R4") (pin "2") (pinfunction "2_2") (pintype "passive"))
    )
    (net (code "33") (name "I2C2_SCL") (class "Default")
      (node (ref "IC1") (pin "47") (pinfunction "PB10_47") (pintype "bidirectional"))
      (node (ref "R1") (pin "P$1") (pinfunction "1_P$1") (pintype "passive"))
      (node (ref "U$5") (pin "25") (pinfunction "SCLK_25") (pintype "input"))
      (node (ref "U8") (pin "6") (pinfunction "SCL_6") (pintype "bidirectional"))
    )
    (net (code "34") (name "I2C2_SDA") (class "Default")
      (node (ref "IC1") (pin "48") (pinfunction "PB11_48") (pintype "bidirectional"))
      (node (ref "R2") (pin "P$1") (pinfunction "1_P$1") (pintype "passive"))
      (node (ref "U$5") (pin "24") (pinfunction "SDATA_24") (pintype "bidirectional"))
      (node (ref "U8") (pin "5") (pinfunction "SDA_5") (pintype "bidirectional"))
    )
    (net (code "35") (name "I2C3_SCL---") (class "Default")
      (node (ref "IC1") (pin "67") (pinfunction "PA8_67") (pintype "bidirectional"))
    )
    (net (code "36") (name "JTCK-SWCLK") (class "Default")
      (node (ref "IC1") (pin "76") (pinfunction "PA14_76") (pintype "bidirectional"))
      (node (ref "J6") (pin "4") (pinfunction "S_4") (pintype "passive"))
    )
    (net (code "37") (name "JTDI") (class "Default")
      (node (ref "IC1") (pin "77") (pinfunction "PA15_77") (pintype "bidirectional"))
      (node (ref "J6") (pin "8") (pinfunction "S_8") (pintype "passive"))
    )
    (net (code "38") (name "JTDO") (class "Default")
      (node (ref "IC1") (pin "89") (pinfunction "PB3_89") (pintype "bidirectional"))
      (node (ref "J6") (pin "6") (pinfunction "S_6") (pintype "passive"))
    )
    (net (code "39") (name "JTMS-SWDIO") (class "Default")
      (node (ref "IC1") (pin "72") (pinfunction "PA13_72") (pintype "bidirectional"))
      (node (ref "J6") (pin "2") (pinfunction "S_2") (pintype "passive"))
    )
    (net (code "40") (name "LED_AMBER") (class "Default")
      (node (ref "IC1") (pin "1") (pinfunction "PE2_1") (pintype "bidirectional"))
      (node (ref "R14") (pin "1") (pinfunction "1_1") (pintype "passive"))
    )
    (net (code "41") (name "LED_BLUE") (class "Default")
      (node (ref "IC1") (pin "2") (pinfunction "PE3_2") (pintype "bidirectional"))
      (node (ref "R15") (pin "1") (pinfunction "1_1") (pintype "passive"))
    )
    (net (code "42") (name "LED_RED") (class "Default")
      (node (ref "IC1") (pin "38") (pinfunction "PE7_38") (pintype "bidirectional"))
      (node (ref "R17") (pin "1") (pinfunction "1_1") (pintype "passive"))
    )
    (net (code "43") (name "MAG_DRDY---") (class "Default")
      (node (ref "IC1") (pin "36") (pinfunction "PB1_36") (pintype "bidirectional"))
    )
    (net (code "44") (name "Net-(C3-1)") (class "Default")
      (node (ref "C3") (pin "P$1") (pinfunction "1_P$1") (pintype "passive"))
      (node (ref "IC1") (pin "12") (pinfunction "OSC_IN_12") (pintype "input"))
      (node (ref "X1") (pin "3") (pinfunction "3_3") (pintype "bidirectional"))
    )
    (net (code "45") (name "Net-(C4-2)") (class "Default")
      (node (ref "C4") (pin "P$2") (pinfunction "2_P$2") (pintype "passive"))
      (node (ref "IC1") (pin "13") (pinfunction "OSC_OUT_13") (pintype "output"))
      (node (ref "X1") (pin "1") (pinfunction "1_1") (pintype "bidirectional"))
    )
    (net (code "46") (name "Net-(D1-A)") (class "Default")
      (node (ref "D1") (pin "ANODE") (pinfunction "A_ANODE") (pintype "passive"))
      (node (ref "L8") (pin "P$1") (pinfunction "1_P$1") (pintype "passive"))
    )
    (net (code "47") (name "Net-(IC1B-VCAP_1)") (class "Default")
      (node (ref "C11") (pin "1") (pinfunction "1_1") (pintype "passive"))
      (node (ref "IC1") (pin "49") (pinfunction "VCAP_1_49") (pintype "power_in"))
    )
    (net (code "48") (name "Net-(IC1B-VCAP_2)") (class "Default")
      (node (ref "C12") (pin "1") (pinfunction "1_1") (pintype "passive"))
      (node (ref "IC1") (pin "73") (pinfunction "VCAP_2_73") (pintype "power_in"))
    )
    (net (code "49") (name "Net-(IC1N-BOOT0)") (class "Default")
      (node (ref "BOOT0") (pin "P$1") (pinfunction "P$1_P$1") (pintype "passive"))
      (node (ref "IC1") (pin "94") (pinfunction "BOOT0_94") (pintype "input"))
      (node (ref "R18") (pin "2") (pinfunction "2_2") (pintype "passive"))
    )
    (net (code "50") (name "Net-(J1A-S)") (class "Default")
      (node (ref "J1") (pin "1") (pinfunction "S_1") (pintype "passive"))
      (node (ref "L2") (pin "P$2") (pinfunction "2_P$2") (pintype "passive"))
    )
    (net (code "51") (name "Net-(J2A-S)") (class "Default")
      (node (ref "J2") (pin "1") (pinfunction "S_1") (pintype "passive"))
      (node (ref "JP2") (pin "2") (pinfunction "2_2") (pintype "passive"))
    )
    (net (code "52") (name "Net-(J5-4)") (class "Default")
      (node (ref "J5") (pin "ID") (pinfunction "4_ID") (pintype "passive"))
      (node (ref "R7") (pin "1") (pinfunction "1_1") (pintype "passive"))
    )
    (net (code "53") (name "Net-(LED1-PadC)") (class "Default")
      (node (ref "LED1") (pin "C") (pinfunction "C_C") (pintype "passive"))
      (node (ref "R13") (pin "2") (pinfunction "2_2") (pintype "passive"))
    )
    (net (code "54") (name "Net-(LED2-PadC)") (class "Default")
      (node (ref "LED2") (pin "C") (pinfunction "C_C") (pintype "passive"))
      (node (ref "R14") (pin "2") (pinfunction "2_2") (pintype "passive"))
    )
    (net (code "55") (name "Net-(LED3-PadC)") (class "Default")
      (node (ref "LED3") (pin "C") (pinfunction "C_C") (pintype "passive"))
      (node (ref "R15") (pin "2") (pinfunction "2_2") (pintype "passive"))
    )
    (net (code "56") (name "Net-(LED4-PadC)") (class "Default")
      (node (ref "LED4") (pin "C") (pinfunction "C_C") (pintype "passive"))
      (node (ref "R17") (pin "2") (pinfunction "2_2") (pintype "passive"))
    )
    (net (code "57") (name "Net-(U$5-BYPASS_CLKIN_N)") (class "Default")
      (node (ref "R19") (pin "1") (pinfunction "1_1") (pintype "passive"))
      (node (ref "U$5") (pin "8") (pinfunction "BYPASS_CLKIN_N_8") (pintype "input"))
    )
    (net (code "58") (name "Net-(U$5-SER_DATAIN_N)") (class "Default")
      (node (ref "R20") (pin "1") (pinfunction "1_1") (pintype "passive"))
      (node (ref "U$5") (pin "10") (pinfunction "SER_DATAIN_N_10") (pintype "input"))
    )
    (net (code "59") (name "Net-(U1-BP)") (class "Default")
      (node (ref "C13") (pin "1") (pinfunction "1_1") (pintype "passive"))
      (node (ref "U1") (pin "4") (pinfunction "BP_4") (pintype "input"))
    )
    (net (code "60") (name "Net-(U12-PLLFILT)") (class "Default")
      (node (ref "C25") (pin "1") (pinfunction "1_1") (pintype "passive"))
      (node (ref "U12") (pin "14") (pinfunction "PLLFILT_14") (pintype "bidirectional"))
    )
    (net (code "61") (name "OTG_FS_ID") (class "Default")
      (node (ref "IC1") (pin "69") (pinfunction "PA10_69") (pintype "bidirectional"))
      (node (ref "R7") (pin "2") (pinfunction "2_2") (pintype "passive"))
    )
    (net (code "62") (name "OTG_FS_N") (class "Default")
      (node (ref "IC1") (pin "70") (pinfunction "PA11_70") (pintype "bidirectional"))
      (node (ref "R6") (pin "2") (pinfunction "2_2") (pintype "passive"))
    )
    (net (code "63") (name "OTG_FS_P") (class "Default")
      (node (ref "IC1") (pin "71") (pinfunction "PA12_71") (pintype "bidirectional"))
      (node (ref "R8") (pin "2") (pinfunction "2_2") (pintype "passive"))
    )
    (net (code "64") (name "OTG_N") (class "Default")
      (node (ref "J5") (pin "D-") (pinfunction "2_D-") (pintype "bidirectional"))
      (node (ref "OTG_DM") (pin "P$1") (pinfunction "P$1_P$1") (pintype "passive"))
      (node (ref "R6") (pin "1") (pinfunction "1_1") (pintype "passive"))
    )
    (net (code "65") (name "OTG_P") (class "Default")
      (node (ref "J5") (pin "D+") (pinfunction "3_D+") (pintype "bidirectional"))
      (node (ref "OTG_DP") (pin "P$1") (pinfunction "P$1_P$1") (pintype "passive"))
      (node (ref "R8") (pin "1") (pinfunction "1_1") (pintype "passive"))
    )
    (net (code "66") (name "PB2-BOOT1") (class "Default")
      (node (ref "BOOT1") (pin "P$1") (pinfunction "P$1_P$1") (pintype "passive"))
      (node (ref "IC1") (pin "37") (pinfunction "PB2_37") (pintype "bidirectional"))
      (node (ref "R5") (pin "1") (pinfunction "1_1") (pintype "passive"))
    )
    (net (code "67") (name "PRES_DRDY---") (class "Default")
      (node (ref "IC1") (pin "35") (pinfunction "PB0_35") (pintype "bidirectional"))
    )
    (net (code "68") (name "SONAR_TX") (class "Default")
      (node (ref "J4") (pin "TX") (pinfunction "S_TX") (pintype "passive"))
      (node (ref "R11") (pin "1") (pinfunction "1_1") (pintype "passive"))
    )
    (net (code "69") (name "SPI1_MOSI---") (class "Default")
      (node (ref "IC1") (pin "32") (pinfunction "PA7_32") (pintype "bidirectional"))
    )
    (net (code "70") (name "SPI2_MISO") (class "Default")
      (node (ref "IC1") (pin "53") (pinfunction "PB14_53") (pintype "bidirectional"))
      (node (ref "U12") (pin "4") (pinfunction "SDO/SA0_4") (pintype "bidirectional"))
    )
    (net (code "71") (name "SPI2_MOSI") (class "Default")
      (node (ref "IC1") (pin "54") (pinfunction "PB15_54") (pintype "bidirectional"))
      (node (ref "U12") (pin "3") (pinfunction "SDA/SDI/SDO_3") (pintype "bidirectional"))
    )
    (net (code "72") (name "SPI2_NSS") (class "Default")
      (node (ref "IC1") (pin "51") (pinfunction "PB12_51") (pintype "bidirectional"))
      (node (ref "U12") (pin "5") (pinfunction "CS_5") (pintype "input"))
    )
    (net (code "73") (name "SPI2_SCK") (class "Default")
      (node (ref "IC1") (pin "52") (pinfunction "PB13_52") (pintype "bidirectional"))
      (node (ref "U12") (pin "2") (pinfunction "SCL/SPC_2") (pintype "input"))
    )
    (net (code "74") (name "TIM1_CH1") (class "Default")
      (node (ref "IC1") (pin "40") (pinfunction "PE9_40") (pintype "bidirectional"))
    )
    (net (code "75") (name "TIM1_CH2") (class "Default")
      (node (ref "IC1") (pin "42") (pinfunction "PE11_42") (pintype "bidirectional"))
    )
    (net (code "76") (name "TIM4_CH2") (class "Default")
      (node (ref "IC1") (pin "60") (pinfunction "PD13_60") (pintype "bidirectional"))
      (node (ref "J4") (pin "PW") (pinfunction "S_PW") (pintype "passive"))
    )
    (net (code "77") (name "TIM4_CH3") (class "Default")
      (node (ref "IC1") (pin "61") (pinfunction "PD14_61") (pintype "bidirectional"))
    )
    (net (code "78") (name "TIM4_CH4") (class "Default")
      (node (ref "IC1") (pin "62") (pinfunction "PD15_62") (pintype "bidirectional"))
    )
    (net (code "79") (name "TIM5_CH1") (class "Default")
      (node (ref "IC1") (pin "23") (pinfunction "PA0_23") (pintype "bidirectional"))
    )
    (net (code "80") (name "TIM5_CH2") (class "Default")
      (node (ref "IC1") (pin "24") (pinfunction "PA1_24") (pintype "bidirectional"))
    )
    (net (code "81") (name "TIM5_CH3_EXPOSURE") (class "Default")
      (node (ref "IC1") (pin "25") (pinfunction "PA2_25") (pintype "bidirectional"))
      (node (ref "U$5") (pin "23") (pinfunction "EXPOSURE_23") (pintype "input"))
    )
    (net (code "82") (name "TIM5_CH4_STANDBY") (class "Default")
      (node (ref "IC1") (pin "26") (pinfunction "PA3_26") (pintype "bidirectional"))
      (node (ref "U$5") (pin "33") (pinfunction "STANDBY_33") (pintype "input"))
    )
    (net (code "83") (name "TIM8_CH3_MASTERCLOCK") (class "Default")
      (node (ref "IC1") (pin "65") (pinfunction "PC8_65") (pintype "bidirectional"))
      (node (ref "U$5") (pin "47") (pinfunction "SYSCLK_47") (pintype "input"))
    )
    (net (code "84") (name "TIM8_CH4_LED_OUT") (class "Default")
      (node (ref "IC1") (pin "66") (pinfunction "PC9_66") (pintype "bidirectional"))
      (node (ref "U$5") (pin "27") (pinfunction "LED_OUT_27") (pintype "output"))
    )
    (net (code "85") (name "UART4_RX") (class "Default")
      (node (ref "IC1") (pin "79") (pinfunction "PC11_79") (pintype "bidirectional"))
      (node (ref "R10") (pin "2") (pinfunction "2_2") (pintype "passive"))
      (node (ref "R11") (pin "2") (pinfunction "2_2") (pintype "passive"))
    )
    (net (code "86") (name "USART2_CK") (class "Default")
      (node (ref "IC1") (pin "88") (pinfunction "PD7_88") (pintype "bidirectional"))
    )
    (net (code "87") (name "USART2_CTS") (class "Default")
      (node (ref "IC1") (pin "84") (pinfunction "PD3_84") (pintype "bidirectional"))
      (node (ref "J2") (pin "4") (pinfunction "S_4") (pintype "passive"))
    )
    (net (code "88") (name "USART2_RTS") (class "Default")
      (node (ref "IC1") (pin "85") (pinfunction "PD4_85") (pintype "bidirectional"))
      (node (ref "J2") (pin "5") (pinfunction "S_5") (pintype "passive"))
    )
    (net (code "89") (name "USART2_RX") (class "Default")
      (node (ref "IC1") (pin "87") (pinfunction "PD6_87") (pintype "bidirectional"))
      (node (ref "J2") (pin "3") (pinfunction "S_3") (pintype "passive"))
      (node (ref "USART2_RX") (pin "P$1") (pinfunction "P$1_P$1") (pintype "passive"))
    )
    (net (code "90") (name "USART2_TX") (class "Default")
      (node (ref "IC1") (pin "86") (pinfunction "PD5_86") (pintype "bidirectional"))
      (node (ref "J2") (pin "2") (pinfunction "S_2") (pintype "passive"))
      (node (ref "USART2_TX") (pin "P$1") (pinfunction "P$1_P$1") (pintype "passive"))
    )
    (net (code "91") (name "USART3_CK") (class "Default")
      (node (ref "IC1") (pin "57") (pinfunction "PD10_57") (pintype "bidirectional"))
    )
    (net (code "92") (name "USART3_CTS") (class "Default")
      (node (ref "IC1") (pin "58") (pinfunction "PD11_58") (pintype "bidirectional"))
      (node (ref "J3") (pin "5") (pinfunction "S_5") (pintype "passive"))
    )
    (net (code "93") (name "USART3_RTS") (class "Default")
      (node (ref "IC1") (pin "59") (pinfunction "PD12_59") (pintype "bidirectional"))
      (node (ref "J3") (pin "4") (pinfunction "S_4") (pintype "passive"))
    )
    (net (code "94") (name "USART3_RX") (class "Default")
      (node (ref "IC1") (pin "56") (pinfunction "PD9_56") (pintype "bidirectional"))
      (node (ref "J3") (pin "2") (pinfunction "S_2") (pintype "passive"))
      (node (ref "USART3_RX") (pin "P$1") (pinfunction "P$1_P$1") (pintype "passive"))
    )
    (net (code "95") (name "USART3_TX") (class "Default")
      (node (ref "IC1") (pin "55") (pinfunction "PD8_55") (pintype "bidirectional"))
      (node (ref "J3") (pin "3") (pinfunction "S_3") (pintype "passive"))
      (node (ref "USART3_TX") (pin "P$1") (pinfunction "P$1_P$1") (pintype "passive"))
    )
    (net (code "96") (name "US_EN1") (class "Default")
      (node (ref "IC1") (pin "39") (pinfunction "PE8_39") (pintype "bidirectional"))
      (node (ref "J4") (pin "RX") (pinfunction "S_RX") (pintype "passive"))
    )
    (net (code "97") (name "US_EN2") (class "Default")
      (node (ref "IC1") (pin "41") (pinfunction "PE10_41") (pintype "bidirectional"))
    )
    (net (code "98") (name "VBUS") (class "Default")
      (node (ref "IC1") (pin "68") (pinfunction "PA9_68") (pintype "bidirectional"))
      (node (ref "J5") (pin "VBUS") (pinfunction "1_VBUS") (pintype "power_in"))
      (node (ref "L8") (pin "P$2") (pinfunction "2_P$2") (pintype "passive"))
      (node (ref "USB_VBUS") (pin "P$1") (pinfunction "P$1_P$1") (pintype "passive"))
    )
    (net (code "99") (name "VDD_3V3") (class "Default")
      (node (ref "C10") (pin "1") (pinfunction "1_1") (pintype "passive"))
      (node (ref "C16") (pin "1") (pinfunction "1_1") (pintype "passive"))
      (node (ref "C18") (pin "1") (pinfunction "1_1") (pintype "passive"))
      (node (ref "C2") (pin "1") (pinfunction "1_1") (pintype "passive"))
      (node (ref "C28") (pin "1") (pinfunction "1_1") (pintype "passive"))
      (node (ref "C29") (pin "1") (pinfunction "1_1") (pintype "passive"))
      (node (ref "C30") (pin "1") (pinfunction "1_1") (pintype "passive"))
      (node (ref "C31") (pin "1") (pinfunction "1_1") (pintype "passive"))
      (node (ref "C32") (pin "1") (pinfunction "1_1") (pintype "passive"))
      (node (ref "C5") (pin "1") (pinfunction "1_1") (pintype "passive"))
      (node (ref "C6") (pin "A") (pinfunction "+_A") (pintype "passive"))
      (node (ref "C8") (pin "1") (pinfunction "1_1") (pintype "passive"))
      (node (ref "C9") (pin "1") (pinfunction "1_1") (pintype "passive"))
      (node (ref "IC1") (pin "100") (pinfunction "VDD_100") (pintype "power_in"))
      (node (ref "IC1") (pin "11") (pinfunction "VDD_11") (pintype "power_in"))
      (node (ref "IC1") (pin "19") (pinfunction "VDD_19") (pintype "power_in"))
      (node (ref "IC1") (pin "28") (pinfunction "VDD_28") (pintype "power_in"))
      (node (ref "IC1") (pin "43") (pinfunction "PE12_43") (pintype "bidirectional"))
      (node (ref "IC1") (pin "50") (pinfunction "VDD_50") (pintype "power_in"))
      (node (ref "IC1") (pin "6") (pinfunction "VBAT_6") (pintype "power_in"))
      (node (ref "IC1") (pin "75") (pinfunction "VDD_75") (pintype "power_in"))
      (node (ref "J6") (pin "1") (pinfunction "S_1") (pintype "passive"))
      (node (ref "JP1") (pin "3") (pinfunction "3_3") (pintype "passive"))
      (node (ref "L11") (pin "P$1") (pinfunction "1_P$1") (pintype "passive"))
      (node (ref "LED1") (pin "A") (pinfunction "A_A") (pintype "passive"))
      (node (ref "LED2") (pin "A") (pinfunction "A_A") (pintype "passive"))
      (node (ref "LED3") (pin "A") (pinfunction "A_A") (pintype "passive"))
      (node (ref "LED4") (pin "A") (pinfunction "A_A") (pintype "passive"))
      (node (ref "R1") (pin "P$2") (pinfunction "2_P$2") (pintype "passive"))
      (node (ref "R16") (pin "2") (pinfunction "2_2") (pintype "passive"))
      (node (ref "R19") (pin "2") (pinfunction "2_2") (pintype "passive"))
      (node (ref "R2") (pin "P$2") (pinfunction "2_P$2") (pintype "passive"))
      (node (ref "R20") (pin "2") (pinfunction "2_2") (pintype "passive"))
      (node (ref "R9") (pin "2") (pinfunction "2_2") (pintype "passive"))
      (node (ref "U$5") (pin "1") (pinfunction "VDD_1") (pintype "input"))
      (node (ref "U$5") (pin "14") (pinfunction "VDD_14") (pintype "input"))
      (node (ref "U$5") (pin "28") (pinfunction "OE_28") (pintype "input"))
      (node (ref "U$5") (pin "30") (pinfunction "SCTRL_ADR0_30") (pintype "input"))
      (node (ref "U$5") (pin "31") (pinfunction "SCTRL_ADR1_31") (pintype "input"))
      (node (ref "U$5") (pin "6") (pinfunction "VDD_LVDS_6") (pintype "input"))
      (node (ref "U1") (pin "5") (pinfunction "OUT_5") (pintype "passive"))
      (node (ref "U12") (pin "1") (pinfunction "VDD_IO_1") (pintype "bidirectional"))
      (node (ref "U8") (pin "8") (pinfunction "VCC_8") (pintype "power_in"))
      (node (ref "VDD_3V3") (pin "P$1") (pinfunction "P$1_P$1") (pintype "passive"))
    )
    (net (code "100") (name "VDD_3V3_ANALOG") (class "Default")
      (node (ref "C15") (pin "1") (pinfunction "1_1") (pintype "passive"))
      (node (ref "C19") (pin "1") (pinfunction "1_1") (pintype "passive"))
      (node (ref "C20") (pin "1") (pinfunction "1_1") (pintype "passive"))
      (node (ref "C21") (pin "1") (pinfunction "1_1") (pintype "passive"))
      (node (ref "C22") (pin "1") (pinfunction "1_1") (pintype "passive"))
      (node (ref "C23") (pin "1") (pinfunction "1_1") (pintype "passive"))
      (node (ref "C24") (pin "1") (pinfunction "1_1") (pintype "passive"))
      (node (ref "C26") (pin "1") (pinfunction "1_1") (pintype "passive"))
      (node (ref "IC1") (pin "21") (pinfunction "VREF+_21") (pintype "input"))
      (node (ref "IC1") (pin "22") (pinfunction "VDDA_22") (pintype "power_in"))
      (node (ref "L11") (pin "P$2") (pinfunction "2_P$2") (pintype "passive"))
      (node (ref "U$5") (pin "35") (pinfunction "VAA_35") (pintype "input"))
      (node (ref "U$5") (pin "39") (pinfunction "VAA_39") (pintype "input"))
      (node (ref "U$5") (pin "40") (pinfunction "VAA_PIX_40") (pintype "input"))
      (node (ref "U12") (pin "15") (pinfunction "RES_P15_VDD_15") (pintype "bidirectional"))
      (node (ref "U12") (pin "16") (pinfunction "VDD_16") (pintype "bidirectional"))
      (node (ref "VDD_3V3_ANALOG") (pin "P$1") (pinfunction "P$1_P$1") (pintype "passive"))
    )
    (net (code "101") (name "VDD_5V") (class "Default")
      (node (ref "C27") (pin "A") (pinfunction "+_A") (pintype "passive"))
      (node (ref "C7") (pin "1") (pinfunction "1_1") (pintype "passive"))
      (node (ref "D1") (pin "CATHODE") (pinfunction "C_CATHODE") (pintype "passive"))
      (node (ref "JP1") (pin "1") (pinfunction "1_1") (pintype "passive"))
      (node (ref "JP2") (pin "1") (pinfunction "1_1") (pintype "passive"))
      (node (ref "Q1") (pin "4") (pinfunction "S_4") (pintype "passive"))
      (node (ref "R10") (pin "1") (pinfunction "1_1") (pintype "passive"))
      (node (ref "U1") (pin "1") (pinfunction "IN_1") (pintype "input"))
      (node (ref "U1") (pin "3") (pinfunction "EN_3") (pintype "input"))
      (node (ref "VDD_5V") (pin "P$1") (pinfunction "P$1_P$1") (pintype "passive"))
    )
    (net (code "102") (name "VDD_5V_IN") (class "Default")
      (node (ref "L1") (pin "P$1") (pinfunction "1_P$1") (pintype "passive"))
      (node (ref "L2") (pin "P$1") (pinfunction "1_P$1") (pintype "passive"))
      (node (ref "Q1") (pin "1") (pinfunction "D_1") (pintype "passive"))
      (node (ref "Q1") (pin "2") (pinfunction "D1_2") (pintype "passive"))
      (node (ref "Q1") (pin "5") (pinfunction "D2_5") (pintype "passive"))
      (node (ref "Q1") (pin "6") (pinfunction "D3_6") (pintype "passive"))
    )
    (net (code "103") (name "VDD_5V_IN_UART3") (class "Default")
      (node (ref "J3") (pin "1") (pinfunction "S_1") (pintype "passive"))
      (node (ref "L1") (pin "P$2") (pinfunction "2_P$2") (pintype "passive"))
      (node (ref "VDD_5V_IN") (pin "P$1") (pinfunction "P$1_P$1") (pintype "passive"))
    )
    (net (code "104") (name "VDD_SONAR") (class "Default")
      (node (ref "J4") (pin "VDD") (pinfunction "S_VDD") (pintype "passive"))
      (node (ref "JP1") (pin "2") (pinfunction "2_2") (pintype "passive"))
    )
    (net (code "105") (name "unconnected-(J4B-S-PadBW)") (class "Default")
      (node (ref "J4") (pin "BW") (pinfunction "S_BW") (pintype "passive"))
    )
    (net (code "106") (name "unconnected-(U$5-NC-Pad36)") (class "Default")
      (node (ref "U$5") (pin "36") (pinfunction "NC_36") (pintype "no_connect"))
    )
    (net (code "107") (name "unconnected-(U$5-NC-Pad37)") (class "Default")
      (node (ref "U$5") (pin "37") (pinfunction "NC_37") (pintype "no_connect"))
    )
    (net (code "108") (name "unconnected-(U$5-SER_DATAOUT_N-Pad4)") (class "Default")
      (node (ref "U$5") (pin "4") (pinfunction "SER_DATAOUT_N_4") (pintype "output"))
    )
    (net (code "109") (name "unconnected-(U$5-SER_DATAOUT_P-Pad5)") (class "Default")
      (node (ref "U$5") (pin "5") (pinfunction "SER_DATAOUT_P_5") (pintype "output"))
    )
    (net (code "110") (name "unconnected-(U$5-SHFT_CLKOUT_N-Pad2)") (class "Default")
      (node (ref "U$5") (pin "2") (pinfunction "SHFT_CLKOUT_N_2") (pintype "output"))
    )
    (net (code "111") (name "unconnected-(U$5-SHFT_CLKOUT_P-Pad3)") (class "Default")
      (node (ref "U$5") (pin "3") (pinfunction "SHFT_CLKOUT_P_3") (pintype "output"))
    )
    (net (code "112") (name "unconnected-(U$5-STFRM_OUT-Pad26)") (class "Default")
      (node (ref "U$5") (pin "26") (pinfunction "STFRM_OUT_26") (pintype "bidirectional"))
    )
    (net (code "113") (name "unconnected-(U$5-STLN_OUT-Pad22)") (class "Default")
      (node (ref "U$5") (pin "22") (pinfunction "STLN_OUT_22") (pintype "bidirectional"))
    )
    (net (code "114") (name "unconnected-(U8-WP-Pad7)") (class "Default")
      (node (ref "U8") (pin "7") (pinfunction "WP_7") (pintype "bidirectional"))
    )
    (net (code "115") (name "unconnected-(U12-DRDY{slash}INT2-Pad6)") (class "Default")
      (node (ref "U12") (pin "6") (pinfunction "DRDY/INT2_6") (pintype "output"))
    )
    (net (code "116") (name "unconnected-(U12-INT1-Pad7)") (class "Default")
      (node (ref "U12") (pin "7") (pinfunction "INT1_7") (pintype "output"))
    )
    (net (code "117") (name "~{JTRST}") (class "Default")
      (node (ref "IC1") (pin "90") (pinfunction "PB4_90") (pintype "bidirectional"))
      (node (ref "J6") (pin "10") (pinfunction "S_10") (pintype "passive"))
    )
    (net (code "118") (name "~{RESET}") (class "Default")
      (node (ref "!RESET") (pin "P$1") (pinfunction "P$1_P$1") (pintype "passive"))
      (node (ref "C17") (pin "2") (pinfunction "2_2") (pintype "passive"))
      (node (ref "IC1") (pin "14") (pinfunction "NRST_14") (pintype "input"))
      (node (ref "R16") (pin "1") (pinfunction "1_1") (pintype "passive"))
      (node (ref "S1") (pin "A1") (pinfunction "1_A1") (pintype "passive"))
    )
  )
)
